# Reciever.net
KiCad netlist of a schematic drawn in EAGLE
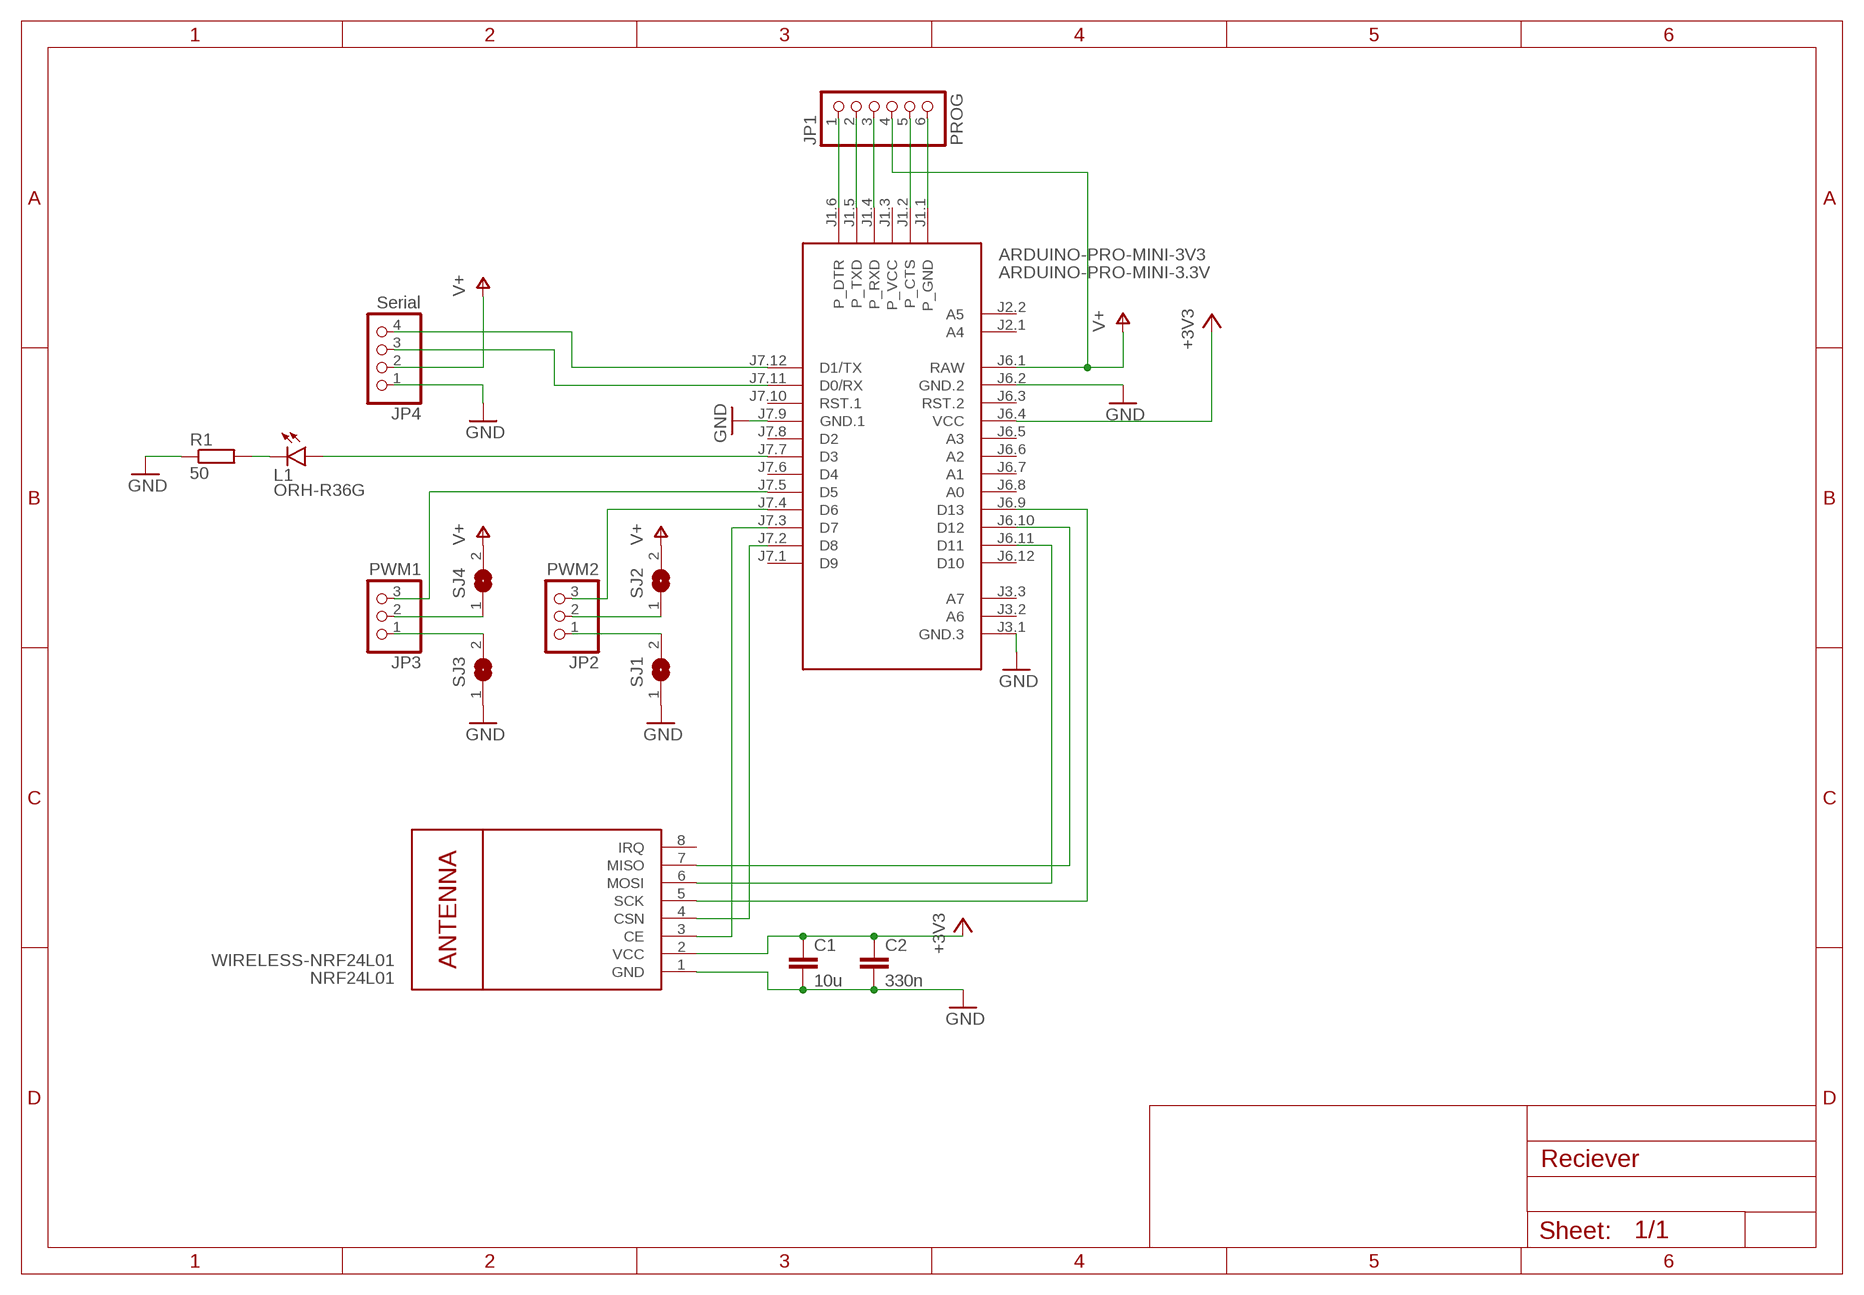
[diagram p0: schematic, sheet 1]

(export (version "E")
  (design (tool "Eeschema 10.0.6"))
  (components
    (comp (ref "ARDUINO-PRO-MINI-3V3")
      (value "ARDUINO-PRO-MINI-3.3V")
      (footprint "eagle-import:ARDUINO-PRO-MINI")
      (libsource (lib "eagle-import") (part "ARDUINO-PRO-MINI-3.3V"))
    )
    (comp (ref "C1")
      (value "10u")
      (footprint "eagle-import:C0805")
      (libsource (lib "eagle-import") (part "C-EUC0805"))
    )
    (comp (ref "C2")
      (value "330n")
      (footprint "eagle-import:C0805")
      (libsource (lib "eagle-import") (part "C-EUC0805"))
    )
    (comp (ref "JP1")
      (value "PROG")
      (footprint "eagle-import:1X06")
      (libsource (lib "eagle-import") (part "PINHD-1X6"))
    )
    (comp (ref "JP2")
      (value "PWM2")
      (footprint "eagle-import:1X03_90")
      (libsource (lib "eagle-import") (part "PINHD-1X3/90"))
    )
    (comp (ref "JP3")
      (value "PWM1")
      (footprint "eagle-import:1X03_90")
      (libsource (lib "eagle-import") (part "PINHD-1X3/90"))
    )
    (comp (ref "JP4")
      (value "Serial")
      (footprint "eagle-import:1X04")
      (libsource (lib "eagle-import") (part "PINHD-1X4"))
    )
    (comp (ref "L1")
      (value "ORH-R36G")
      (footprint "eagle-import:CHIP-LED0603")
      (libsource (lib "eagle-import") (part "LEDCHIP-LED0603"))
    )
    (comp (ref "NRF24L01")
      (value "WIRELESS-NRF24L01")
      (footprint "eagle-import:WIRELESS-NRF24L01")
      (libsource (lib "eagle-import") (part "WIRELESS-NRF24L01"))
    )
    (comp (ref "R1")
      (value "50")
      (footprint "eagle-import:R0603")
      (libsource (lib "eagle-import") (part "R-EU_R0603"))
    )
    (comp (ref "SJ1")
      (value "SJW")
      (footprint "eagle-import:SJW")
      (libsource (lib "eagle-import") (part "SJW"))
    )
    (comp (ref "SJ2")
      (value "SJW")
      (footprint "eagle-import:SJW")
      (libsource (lib "eagle-import") (part "SJW"))
    )
    (comp (ref "SJ3")
      (value "SJW")
      (footprint "eagle-import:SJW")
      (libsource (lib "eagle-import") (part "SJW"))
    )
    (comp (ref "SJ4")
      (value "SJW")
      (footprint "eagle-import:SJW")
      (libsource (lib "eagle-import") (part "SJW"))
    )
  )
  (nets
    (net (code "1") (name "+3V3") (class "Default")
      (node (ref "ARDUINO-PRO-MINI-3V3") (pin "J6.4") (pinfunction "VCC_J6.4") (pintype "power_in"))
      (node (ref "C1") (pin "1") (pinfunction "1_1") (pintype "passive"))
      (node (ref "C2") (pin "1") (pinfunction "1_1") (pintype "passive"))
      (node (ref "NRF24L01") (pin "2") (pinfunction "VCC_2") (pintype "power_in"))
    )
    (net (code "2") (name "GND") (class "Default")
      (node (ref "ARDUINO-PRO-MINI-3V3") (pin "J3.1") (pinfunction "GND.3_J3.1") (pintype "bidirectional"))
      (node (ref "ARDUINO-PRO-MINI-3V3") (pin "J6.2") (pinfunction "GND.2_J6.2") (pintype "power_in"))
      (node (ref "ARDUINO-PRO-MINI-3V3") (pin "J7.9") (pinfunction "GND.1_J7.9") (pintype "power_in"))
      (node (ref "C1") (pin "2") (pinfunction "2_2") (pintype "passive"))
      (node (ref "C2") (pin "2") (pinfunction "2_2") (pintype "passive"))
      (node (ref "JP4") (pin "1") (pinfunction "1_1") (pintype "passive"))
      (node (ref "NRF24L01") (pin "1") (pinfunction "GND_1") (pintype "power_in"))
      (node (ref "R1") (pin "1") (pinfunction "1_1") (pintype "passive"))
      (node (ref "SJ1") (pin "1") (pinfunction "1_1") (pintype "passive"))
      (node (ref "SJ3") (pin "1") (pinfunction "1_1") (pintype "passive"))
    )
    (net (code "3") (name "Net-(ARDUINO-PRO-MINI-3V3-D0{slash}RX)") (class "Default")
      (node (ref "ARDUINO-PRO-MINI-3V3") (pin "J7.11") (pinfunction "D0/RX_J7.11") (pintype "bidirectional"))
      (node (ref "JP4") (pin "3") (pinfunction "3_3") (pintype "passive"))
    )
    (net (code "4") (name "Net-(ARDUINO-PRO-MINI-3V3-D1{slash}TX)") (class "Default")
      (node (ref "ARDUINO-PRO-MINI-3V3") (pin "J7.12") (pinfunction "D1/TX_J7.12") (pintype "bidirectional"))
      (node (ref "JP4") (pin "4") (pinfunction "4_4") (pintype "passive"))
    )
    (net (code "5") (name "Net-(ARDUINO-PRO-MINI-3V3-D3)") (class "Default")
      (node (ref "ARDUINO-PRO-MINI-3V3") (pin "J7.7") (pinfunction "D3_J7.7") (pintype "bidirectional"))
      (node (ref "L1") (pin "A") (pinfunction "A_A") (pintype "passive"))
    )
    (net (code "6") (name "Net-(ARDUINO-PRO-MINI-3V3-D5)") (class "Default")
      (node (ref "ARDUINO-PRO-MINI-3V3") (pin "J7.5") (pinfunction "D5_J7.5") (pintype "bidirectional"))
      (node (ref "JP3") (pin "3") (pinfunction "3_3") (pintype "passive"))
    )
    (net (code "7") (name "Net-(ARDUINO-PRO-MINI-3V3-D6)") (class "Default")
      (node (ref "ARDUINO-PRO-MINI-3V3") (pin "J7.4") (pinfunction "D6_J7.4") (pintype "bidirectional"))
      (node (ref "JP2") (pin "3") (pinfunction "3_3") (pintype "passive"))
    )
    (net (code "8") (name "Net-(ARDUINO-PRO-MINI-3V3-D7)") (class "Default")
      (node (ref "ARDUINO-PRO-MINI-3V3") (pin "J7.3") (pinfunction "D7_J7.3") (pintype "bidirectional"))
      (node (ref "NRF24L01") (pin "3") (pinfunction "CE_3") (pintype "bidirectional"))
    )
    (net (code "9") (name "Net-(ARDUINO-PRO-MINI-3V3-D8)") (class "Default")
      (node (ref "ARDUINO-PRO-MINI-3V3") (pin "J7.2") (pinfunction "D8_J7.2") (pintype "bidirectional"))
      (node (ref "NRF24L01") (pin "4") (pinfunction "CSN_4") (pintype "bidirectional"))
    )
    (net (code "10") (name "Net-(ARDUINO-PRO-MINI-3V3-D11)") (class "Default")
      (node (ref "ARDUINO-PRO-MINI-3V3") (pin "J6.11") (pinfunction "D11_J6.11") (pintype "bidirectional"))
      (node (ref "NRF24L01") (pin "6") (pinfunction "MOSI_6") (pintype "bidirectional"))
    )
    (net (code "11") (name "Net-(ARDUINO-PRO-MINI-3V3-D12)") (class "Default")
      (node (ref "ARDUINO-PRO-MINI-3V3") (pin "J6.10") (pinfunction "D12_J6.10") (pintype "bidirectional"))
      (node (ref "NRF24L01") (pin "7") (pinfunction "MISO_7") (pintype "bidirectional"))
    )
    (net (code "12") (name "Net-(ARDUINO-PRO-MINI-3V3-D13)") (class "Default")
      (node (ref "ARDUINO-PRO-MINI-3V3") (pin "J6.9") (pinfunction "D13_J6.9") (pintype "bidirectional"))
      (node (ref "NRF24L01") (pin "5") (pinfunction "SCK_5") (pintype "bidirectional"))
    )
    (net (code "13") (name "Net-(ARDUINO-PRO-MINI-3V3-P_CTS)") (class "Default")
      (node (ref "ARDUINO-PRO-MINI-3V3") (pin "J1.2") (pinfunction "P_CTS_J1.2") (pintype "bidirectional"))
      (node (ref "JP1") (pin "5") (pinfunction "5_5") (pintype "passive"))
    )
    (net (code "14") (name "Net-(ARDUINO-PRO-MINI-3V3-P_DTR)") (class "Default")
      (node (ref "ARDUINO-PRO-MINI-3V3") (pin "J1.6") (pinfunction "P_DTR_J1.6") (pintype "bidirectional"))
      (node (ref "JP1") (pin "1") (pinfunction "1_1") (pintype "passive"))
    )
    (net (code "15") (name "Net-(ARDUINO-PRO-MINI-3V3-P_GND)") (class "Default")
      (node (ref "ARDUINO-PRO-MINI-3V3") (pin "J1.1") (pinfunction "P_GND_J1.1") (pintype "bidirectional"))
      (node (ref "JP1") (pin "6") (pinfunction "6_6") (pintype "passive"))
    )
    (net (code "16") (name "Net-(ARDUINO-PRO-MINI-3V3-P_RXD)") (class "Default")
      (node (ref "ARDUINO-PRO-MINI-3V3") (pin "J1.4") (pinfunction "P_RXD_J1.4") (pintype "bidirectional"))
      (node (ref "JP1") (pin "3") (pinfunction "3_3") (pintype "passive"))
    )
    (net (code "17") (name "Net-(ARDUINO-PRO-MINI-3V3-P_TXD)") (class "Default")
      (node (ref "ARDUINO-PRO-MINI-3V3") (pin "J1.5") (pinfunction "P_TXD_J1.5") (pintype "bidirectional"))
      (node (ref "JP1") (pin "2") (pinfunction "2_2") (pintype "passive"))
    )
    (net (code "18") (name "Net-(JP2-Pad1)") (class "Default")
      (node (ref "JP2") (pin "1") (pinfunction "1_1") (pintype "passive"))
      (node (ref "SJ1") (pin "2") (pinfunction "2_2") (pintype "passive"))
    )
    (net (code "19") (name "Net-(JP2-Pad2)") (class "Default")
      (node (ref "JP2") (pin "2") (pinfunction "2_2") (pintype "passive"))
      (node (ref "SJ2") (pin "1") (pinfunction "1_1") (pintype "passive"))
    )
    (net (code "20") (name "Net-(JP3-Pad1)") (class "Default")
      (node (ref "JP3") (pin "1") (pinfunction "1_1") (pintype "passive"))
      (node (ref "SJ3") (pin "2") (pinfunction "2_2") (pintype "passive"))
    )
    (net (code "21") (name "Net-(JP3-Pad2)") (class "Default")
      (node (ref "JP3") (pin "2") (pinfunction "2_2") (pintype "passive"))
      (node (ref "SJ4") (pin "1") (pinfunction "1_1") (pintype "passive"))
    )
    (net (code "22") (name "Net-(L1-PadC)") (class "Default")
      (node (ref "L1") (pin "C") (pinfunction "C_C") (pintype "passive"))
      (node (ref "R1") (pin "2") (pinfunction "2_2") (pintype "passive"))
    )
    (net (code "23") (name "V+") (class "Default")
      (node (ref "ARDUINO-PRO-MINI-3V3") (pin "J6.1") (pinfunction "RAW_J6.1") (pintype "power_in"))
      (node (ref "JP1") (pin "4") (pinfunction "4_4") (pintype "passive"))
      (node (ref "JP4") (pin "2") (pinfunction "2_2") (pintype "passive"))
      (node (ref "SJ2") (pin "2") (pinfunction "2_2") (pintype "passive"))
      (node (ref "SJ4") (pin "2") (pinfunction "2_2") (pintype "passive"))
    )
    (net (code "24") (name "unconnected-(ARDUINO-PRO-MINI-3V3-A0-PadJ6.8)") (class "Default")
      (node (ref "ARDUINO-PRO-MINI-3V3") (pin "J6.8") (pinfunction "A0_J6.8") (pintype "bidirectional"))
    )
    (net (code "25") (name "unconnected-(ARDUINO-PRO-MINI-3V3-A1-PadJ6.7)") (class "Default")
      (node (ref "ARDUINO-PRO-MINI-3V3") (pin "J6.7") (pinfunction "A1_J6.7") (pintype "bidirectional"))
    )
    (net (code "26") (name "unconnected-(ARDUINO-PRO-MINI-3V3-A2-PadJ6.6)") (class "Default")
      (node (ref "ARDUINO-PRO-MINI-3V3") (pin "J6.6") (pinfunction "A2_J6.6") (pintype "bidirectional"))
    )
    (net (code "27") (name "unconnected-(ARDUINO-PRO-MINI-3V3-A3-PadJ6.5)") (class "Default")
      (node (ref "ARDUINO-PRO-MINI-3V3") (pin "J6.5") (pinfunction "A3_J6.5") (pintype "bidirectional"))
    )
    (net (code "28") (name "unconnected-(ARDUINO-PRO-MINI-3V3-A4-PadJ2.1)") (class "Default")
      (node (ref "ARDUINO-PRO-MINI-3V3") (pin "J2.1") (pinfunction "A4_J2.1") (pintype "bidirectional"))
    )
    (net (code "29") (name "unconnected-(ARDUINO-PRO-MINI-3V3-A5-PadJ2.2)") (class "Default")
      (node (ref "ARDUINO-PRO-MINI-3V3") (pin "J2.2") (pinfunction "A5_J2.2") (pintype "bidirectional"))
    )
    (net (code "30") (name "unconnected-(ARDUINO-PRO-MINI-3V3-A6-PadJ3.2)") (class "Default")
      (node (ref "ARDUINO-PRO-MINI-3V3") (pin "J3.2") (pinfunction "A6_J3.2") (pintype "bidirectional"))
    )
    (net (code "31") (name "unconnected-(ARDUINO-PRO-MINI-3V3-A7-PadJ3.3)") (class "Default")
      (node (ref "ARDUINO-PRO-MINI-3V3") (pin "J3.3") (pinfunction "A7_J3.3") (pintype "bidirectional"))
    )
    (net (code "32") (name "unconnected-(ARDUINO-PRO-MINI-3V3-D2-PadJ7.8)") (class "Default")
      (node (ref "ARDUINO-PRO-MINI-3V3") (pin "J7.8") (pinfunction "D2_J7.8") (pintype "bidirectional"))
    )
    (net (code "33") (name "unconnected-(ARDUINO-PRO-MINI-3V3-D4-PadJ7.6)") (class "Default")
      (node (ref "ARDUINO-PRO-MINI-3V3") (pin "J7.6") (pinfunction "D4_J7.6") (pintype "bidirectional"))
    )
    (net (code "34") (name "unconnected-(ARDUINO-PRO-MINI-3V3-D9-PadJ7.1)") (class "Default")
      (node (ref "ARDUINO-PRO-MINI-3V3") (pin "J7.1") (pinfunction "D9_J7.1") (pintype "bidirectional"))
    )
    (net (code "35") (name "unconnected-(ARDUINO-PRO-MINI-3V3-D10-PadJ6.12)") (class "Default")
      (node (ref "ARDUINO-PRO-MINI-3V3") (pin "J6.12") (pinfunction "D10_J6.12") (pintype "bidirectional"))
    )
    (net (code "36") (name "unconnected-(ARDUINO-PRO-MINI-3V3-P_VCC-PadJ1.3)") (class "Default")
      (node (ref "ARDUINO-PRO-MINI-3V3") (pin "J1.3") (pinfunction "P_VCC_J1.3") (pintype "bidirectional"))
    )
    (net (code "37") (name "unconnected-(ARDUINO-PRO-MINI-3V3-RST.1-PadJ7.10)") (class "Default")
      (node (ref "ARDUINO-PRO-MINI-3V3") (pin "J7.10") (pinfunction "RST.1_J7.10") (pintype "bidirectional"))
    )
    (net (code "38") (name "unconnected-(ARDUINO-PRO-MINI-3V3-RST.2-PadJ6.3)") (class "Default")
      (node (ref "ARDUINO-PRO-MINI-3V3") (pin "J6.3") (pinfunction "RST.2_J6.3") (pintype "bidirectional"))
    )
    (net (code "39") (name "unconnected-(NRF24L01-IRQ-Pad8)") (class "Default")
      (node (ref "NRF24L01") (pin "8") (pinfunction "IRQ_8") (pintype "bidirectional"))
    )
  )
)
